# LCD.net
KiCad netlist of a schematic drawn in Altium Designer
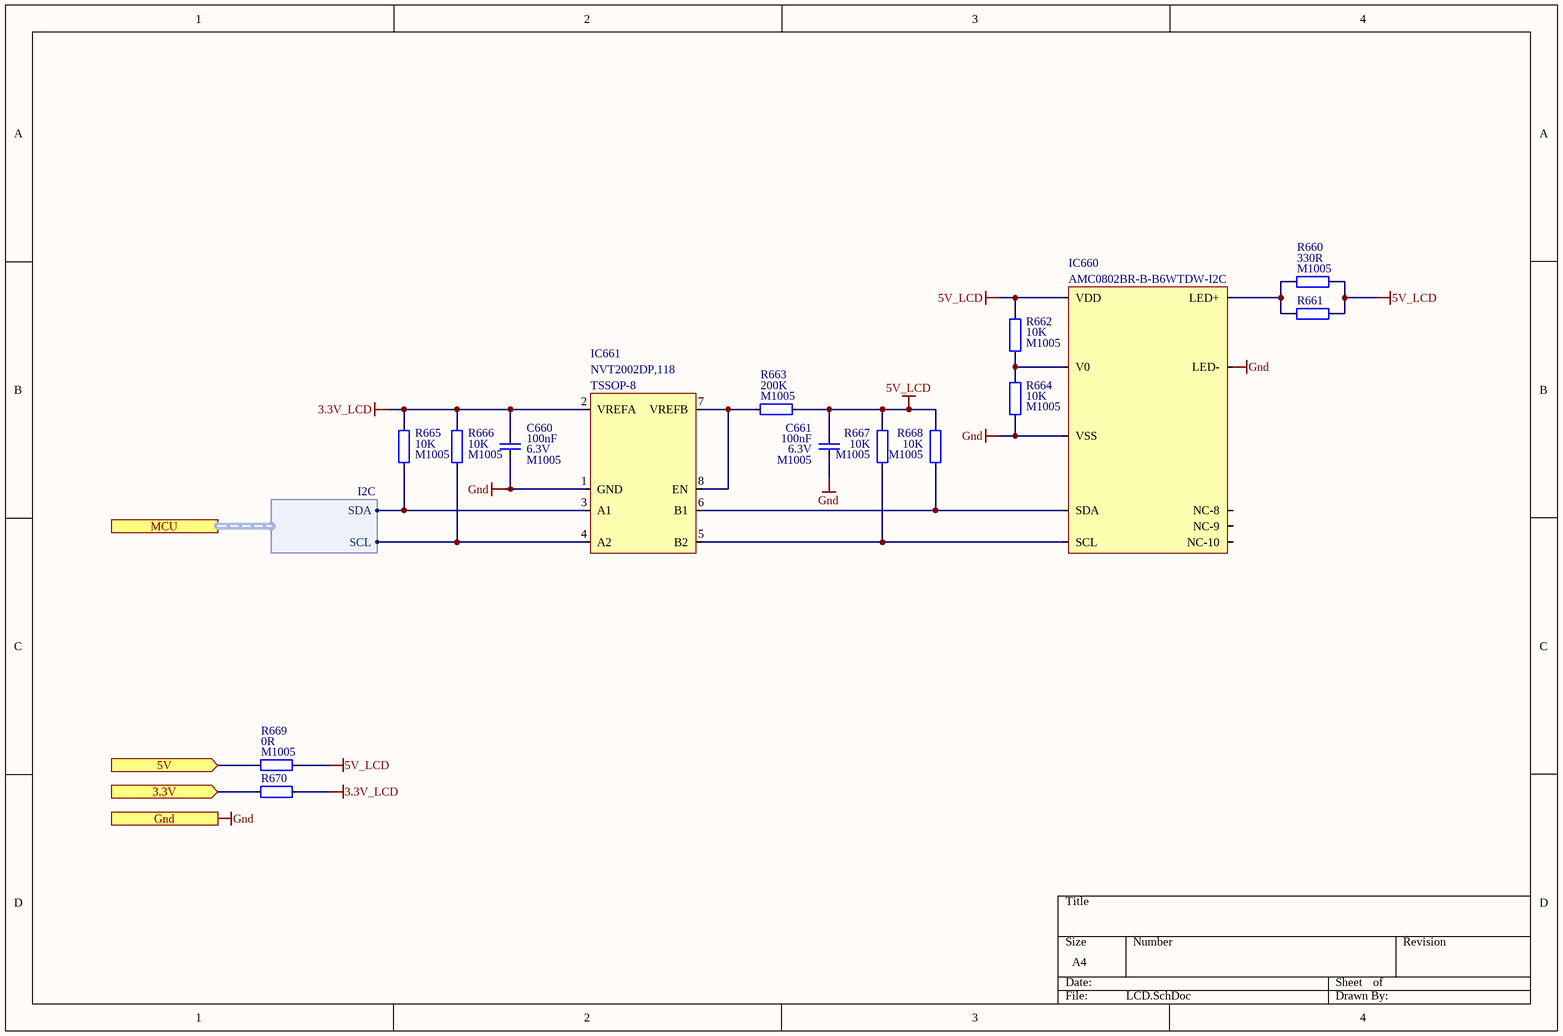
[diagram p0: LCD.SchDoc]

(export (version "E")
  (design (tool "Eeschema 10.0.6"))
  (components
    (comp (ref "C660")
      (value "100nF")
      (footprint "Capacitor_Ceramic_M1005_I0402")
      (description "Cap, Cer, 100nF, 6.3V, M1005")
      (fields
        (field (name "VOLTAGE") "6.3V")
        (field (name "MANUFACTURER PART NUMBER") "04026D104KAT4A")
        (field (name "MANUFACTURER") "Kyocera")
        (field (name "PACKAGE") "M1005")
      )
      (libsource (lib "Capacitor") (part "Capacitor_Ceramic"))
    )
    (comp (ref "C661")
      (value "100nF")
      (footprint "Capacitor_Ceramic_M1005_I0402")
      (description "Cap, Cer, 100nF, 6.3V, M1005")
      (fields
        (field (name "VOLTAGE") "6.3V")
        (field (name "MANUFACTURER PART NUMBER") "04026D104KAT4A")
        (field (name "MANUFACTURER") "Kyocera")
        (field (name "PACKAGE") "M1005")
      )
      (libsource (lib "Capacitor") (part "Capacitor_Ceramic"))
    )
    (comp (ref "IC660")
      (value "Orient, AMC0802BR-B-B6WTDW-I2C")
      (footprint "Orient, AMC0802BR-B-B6WTDW-I2C")
      (description "Module, Display, Lcd, 2 Lines, I2C")
      (fields
        (field (name "MANUFACTURER") "Orient Display")
        (field (name "MANUFACTURER PART NUMBER") "AMC0802BR-B-B6WTDW-I2C")
      )
      (libsource (lib "Module - LCD") (part "Orient, AMC0802BR-B-B6WTDW-I2C"))
    )
    (comp (ref "IC661")
      (value "Voltage Translator, I2C - Nxp, NVT2002DP")
      (footprint "TSSOP-8, Body 3mm, Pitch 0.65mm")
      (description "IC, Interface, I2C, TSSOP-8")
      (fields
        (field (name "MANUFACTURER") "Nxp")
        (field (name "MANUFACTURER PART NUMBER") "NVT2002DP,118")
        (field (name "PACKAGE") "TSSOP-8")
      )
      (libsource (lib "IC - Interface") (part "Voltage Translator, I2C - Nxp, NVT2002DP"))
    )
    (comp (ref "R660")
      (value "330R")
      (footprint "Resistor_Smd_M1005_I0402")
      (description "Res, 330R, 1%, M1005")
      (fields
        (field (name "TOLERANCE") "1%")
        (field (name "MANUFACTURER") "Yageo")
        (field (name "PACKAGE") "M1005")
      )
      (libsource (lib "Resistor") (part "Resistor"))
    )
    (comp (ref "R661")
      (value "Resistor")
      (footprint "Resistor_Smd_M1005_I0402")
      (description "Res, 330R, 1%, M1005")
      (fields (field (name "TOLERANCE") "1%") (field (name "MANUFACTURER") "Yageo"))
      (libsource (lib "Resistor") (part "Resistor"))
    )
    (comp (ref "R662")
      (value "10K")
      (footprint "Resistor_Smd_M1005_I0402")
      (description "Res, 10K, 1%, M1005")
      (fields
        (field (name "TOLERANCE") "1%")
        (field (name "MANUFACTURER") "Yageo")
        (field (name "PACKAGE") "M1005")
      )
      (libsource (lib "Resistor") (part "Resistor"))
    )
    (comp (ref "R663")
      (value "200K")
      (footprint "Resistor_Smd_M1005_I0402")
      (description "Res, 200K, 1%, M1005")
      (fields
        (field (name "TOLERANCE") "1%")
        (field (name "MANUFACTURER") "Yageo")
        (field (name "PACKAGE") "M1005")
      )
      (libsource (lib "Resistor") (part "Resistor"))
    )
    (comp (ref "R664")
      (value "10K")
      (footprint "Resistor_Smd_M1005_I0402")
      (description "Res, 10K, 1%, M1005")
      (fields
        (field (name "TOLERANCE") "1%")
        (field (name "MANUFACTURER") "Yageo")
        (field (name "PACKAGE") "M1005")
      )
      (libsource (lib "Resistor") (part "Resistor"))
    )
    (comp (ref "R665")
      (value "10K")
      (footprint "Resistor_Smd_M1005_I0402")
      (description "Res, 10K, 1%, M1005")
      (fields
        (field (name "TOLERANCE") "1%")
        (field (name "MANUFACTURER") "Yageo")
        (field (name "PACKAGE") "M1005")
      )
      (libsource (lib "Resistor") (part "Resistor"))
    )
    (comp (ref "R666")
      (value "10K")
      (footprint "Resistor_Smd_M1005_I0402")
      (description "Res, 10K, 1%, M1005")
      (fields
        (field (name "TOLERANCE") "1%")
        (field (name "MANUFACTURER") "Yageo")
        (field (name "PACKAGE") "M1005")
      )
      (libsource (lib "Resistor") (part "Resistor"))
    )
    (comp (ref "R667")
      (value "10K")
      (footprint "Resistor_Smd_M1005_I0402")
      (description "Res, 10K, 1%, M1005")
      (fields
        (field (name "TOLERANCE") "1%")
        (field (name "MANUFACTURER") "Yageo")
        (field (name "PACKAGE") "M1005")
      )
      (libsource (lib "Resistor") (part "Resistor"))
    )
    (comp (ref "R668")
      (value "10K")
      (footprint "Resistor_Smd_M1005_I0402")
      (description "Res, 10K, 1%, M1005")
      (fields
        (field (name "TOLERANCE") "1%")
        (field (name "MANUFACTURER") "Yageo")
        (field (name "PACKAGE") "M1005")
      )
      (libsource (lib "Resistor") (part "Resistor"))
    )
    (comp (ref "R669")
      (value "0R")
      (footprint "Resistor_Smd_M1005_I0402")
      (description "Res, 0R, M1005")
      (fields
        (field (name "MANUFACTURER") "Yageo")
        (field (name "MANUFACTURER PART NUMBER") "RC0402FR-070RL")
        (field (name "PACKAGE") "M1005")
      )
      (libsource (lib "Resistor") (part "Resistor"))
    )
    (comp (ref "R670")
      (value "Resistor")
      (footprint "Resistor_Smd_M1005_I0402")
      (description "Res, 0R, M1005")
      (fields
        (field (name "MANUFACTURER") "Yageo")
        (field (name "MANUFACTURER PART NUMBER") "RC0402FR-070RL")
      )
      (libsource (lib "Resistor") (part "Resistor"))
    )
  )
  (nets
    (net (code "2") (name "/3.3V") (class "Default")
      (node (ref "R670") (pin "1") (pinfunction "1_1") (pintype "passive"))
    )
    (net (code "3") (name "/5V") (class "Default")
      (node (ref "R669") (pin "1") (pinfunction "1_1") (pintype "passive"))
    )
    (net (code "5") (name "3.3V_LCD") (class "Default")
      (node (ref "C660") (pin "1") (pinfunction "1_1") (pintype "passive"))
      (node (ref "IC661") (pin "2") (pinfunction "VREFA_2") (pintype "passive"))
      (node (ref "R665") (pin "1") (pinfunction "1_1") (pintype "passive"))
      (node (ref "R666") (pin "1") (pinfunction "1_1") (pintype "passive"))
      (node (ref "R670") (pin "2") (pinfunction "2_2") (pintype "passive"))
    )
    (net (code "6") (name "5V_LCD") (class "Default")
      (node (ref "C661") (pin "1") (pinfunction "1_1") (pintype "passive"))
      (node (ref "IC660") (pin "VDD") (pinfunction "VDD_VDD") (pintype "passive"))
      (node (ref "R660") (pin "2") (pinfunction "2_2") (pintype "passive"))
      (node (ref "R661") (pin "2") (pinfunction "2_2") (pintype "passive"))
      (node (ref "R662") (pin "1") (pinfunction "1_1") (pintype "passive"))
      (node (ref "R663") (pin "2") (pinfunction "2_2") (pintype "passive"))
      (node (ref "R667") (pin "1") (pinfunction "1_1") (pintype "passive"))
      (node (ref "R668") (pin "1") (pinfunction "1_1") (pintype "passive"))
      (node (ref "R669") (pin "2") (pinfunction "2_2") (pintype "passive"))
    )
    (net (code "7") (name "Gnd") (class "Default")
      (node (ref "C660") (pin "2") (pinfunction "2_2") (pintype "passive"))
      (node (ref "C661") (pin "2") (pinfunction "2_2") (pintype "passive"))
      (node (ref "IC660") (pin "LED-") (pinfunction "LED-_LED-") (pintype "passive"))
      (node (ref "IC660") (pin "VSS") (pinfunction "VSS_VSS") (pintype "passive"))
      (node (ref "IC661") (pin "1") (pinfunction "GND_1") (pintype "passive"))
      (node (ref "R664") (pin "2") (pinfunction "2_2") (pintype "passive"))
    )
    (net (code "8") (name "Net-(IC660-PadLED+)") (class "Default")
      (node (ref "IC660") (pin "LED+") (pinfunction "LED+_LED+") (pintype "passive"))
      (node (ref "R660") (pin "1") (pinfunction "1_1") (pintype "passive"))
      (node (ref "R661") (pin "1") (pinfunction "1_1") (pintype "passive"))
    )
    (net (code "9") (name "Net-(IC660-PadV0)") (class "Default")
      (node (ref "IC660") (pin "V0") (pinfunction "V0_V0") (pintype "passive"))
      (node (ref "R662") (pin "2") (pinfunction "2_2") (pintype "passive"))
      (node (ref "R664") (pin "1") (pinfunction "1_1") (pintype "passive"))
    )
    (net (code "10") (name "Net-(IC661-A1)") (class "Default")
      (node (ref "IC661") (pin "3") (pinfunction "A1_3") (pintype "passive"))
      (node (ref "R665") (pin "2") (pinfunction "2_2") (pintype "passive"))
    )
    (net (code "11") (name "Net-(IC661-A2)") (class "Default")
      (node (ref "IC661") (pin "4") (pinfunction "A2_4") (pintype "passive"))
      (node (ref "R666") (pin "2") (pinfunction "2_2") (pintype "passive"))
    )
    (net (code "12") (name "Net-(IC661-B1)") (class "Default")
      (node (ref "IC660") (pin "SDA") (pinfunction "SDA_SDA") (pintype "passive"))
      (node (ref "IC661") (pin "6") (pinfunction "B1_6") (pintype "passive"))
      (node (ref "R668") (pin "2") (pinfunction "2_2") (pintype "passive"))
    )
    (net (code "13") (name "Net-(IC661-B2)") (class "Default")
      (node (ref "IC660") (pin "SCL") (pinfunction "SCL_SCL") (pintype "passive"))
      (node (ref "IC661") (pin "5") (pinfunction "B2_5") (pintype "passive"))
      (node (ref "R667") (pin "2") (pinfunction "2_2") (pintype "passive"))
    )
    (net (code "14") (name "Net-(IC661-EN)") (class "Default")
      (node (ref "IC661") (pin "7") (pinfunction "VREFB_7") (pintype "passive"))
      (node (ref "IC661") (pin "8") (pinfunction "EN_8") (pintype "passive"))
      (node (ref "R663") (pin "1") (pinfunction "1_1") (pintype "passive"))
    )
    (net (code "15") (name "unconnected-(IC660-PadNC-8)") (class "Default")
      (node (ref "IC660") (pin "NC-8") (pinfunction "NC-8_NC-8") (pintype "passive"))
    )
    (net (code "16") (name "unconnected-(IC660-PadNC-9)") (class "Default")
      (node (ref "IC660") (pin "NC-9") (pinfunction "NC-9_NC-9") (pintype "passive"))
    )
    (net (code "17") (name "unconnected-(IC660-PadNC-10)") (class "Default")
      (node (ref "IC660") (pin "NC-10") (pinfunction "NC-10_NC-10") (pintype "passive"))
    )
  )
)
